# solar-counter-v1_0.net
KiCad netlist of a schematic drawn in EAGLE
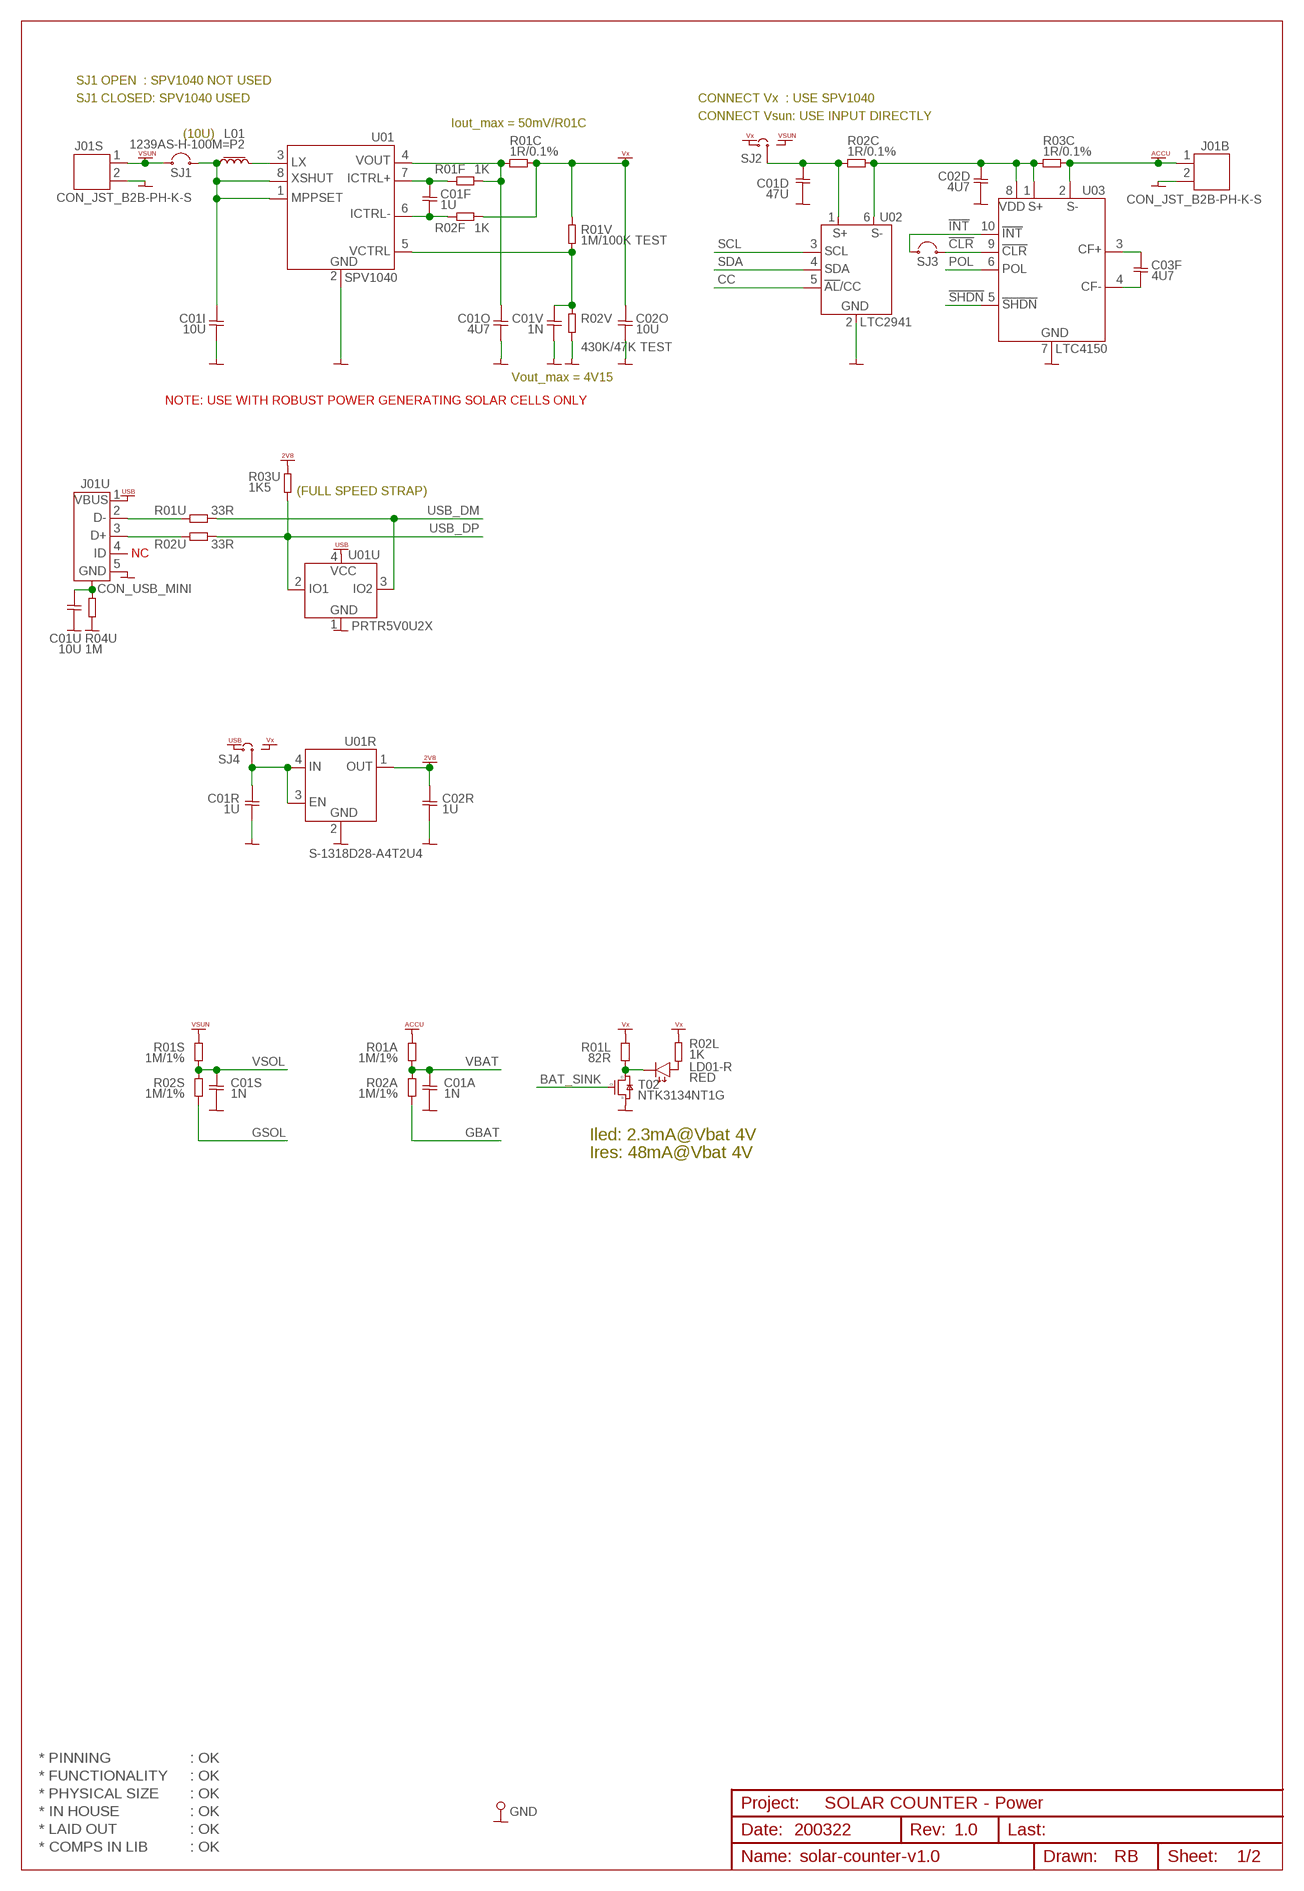
[diagram p0: schematic, sheet 1]
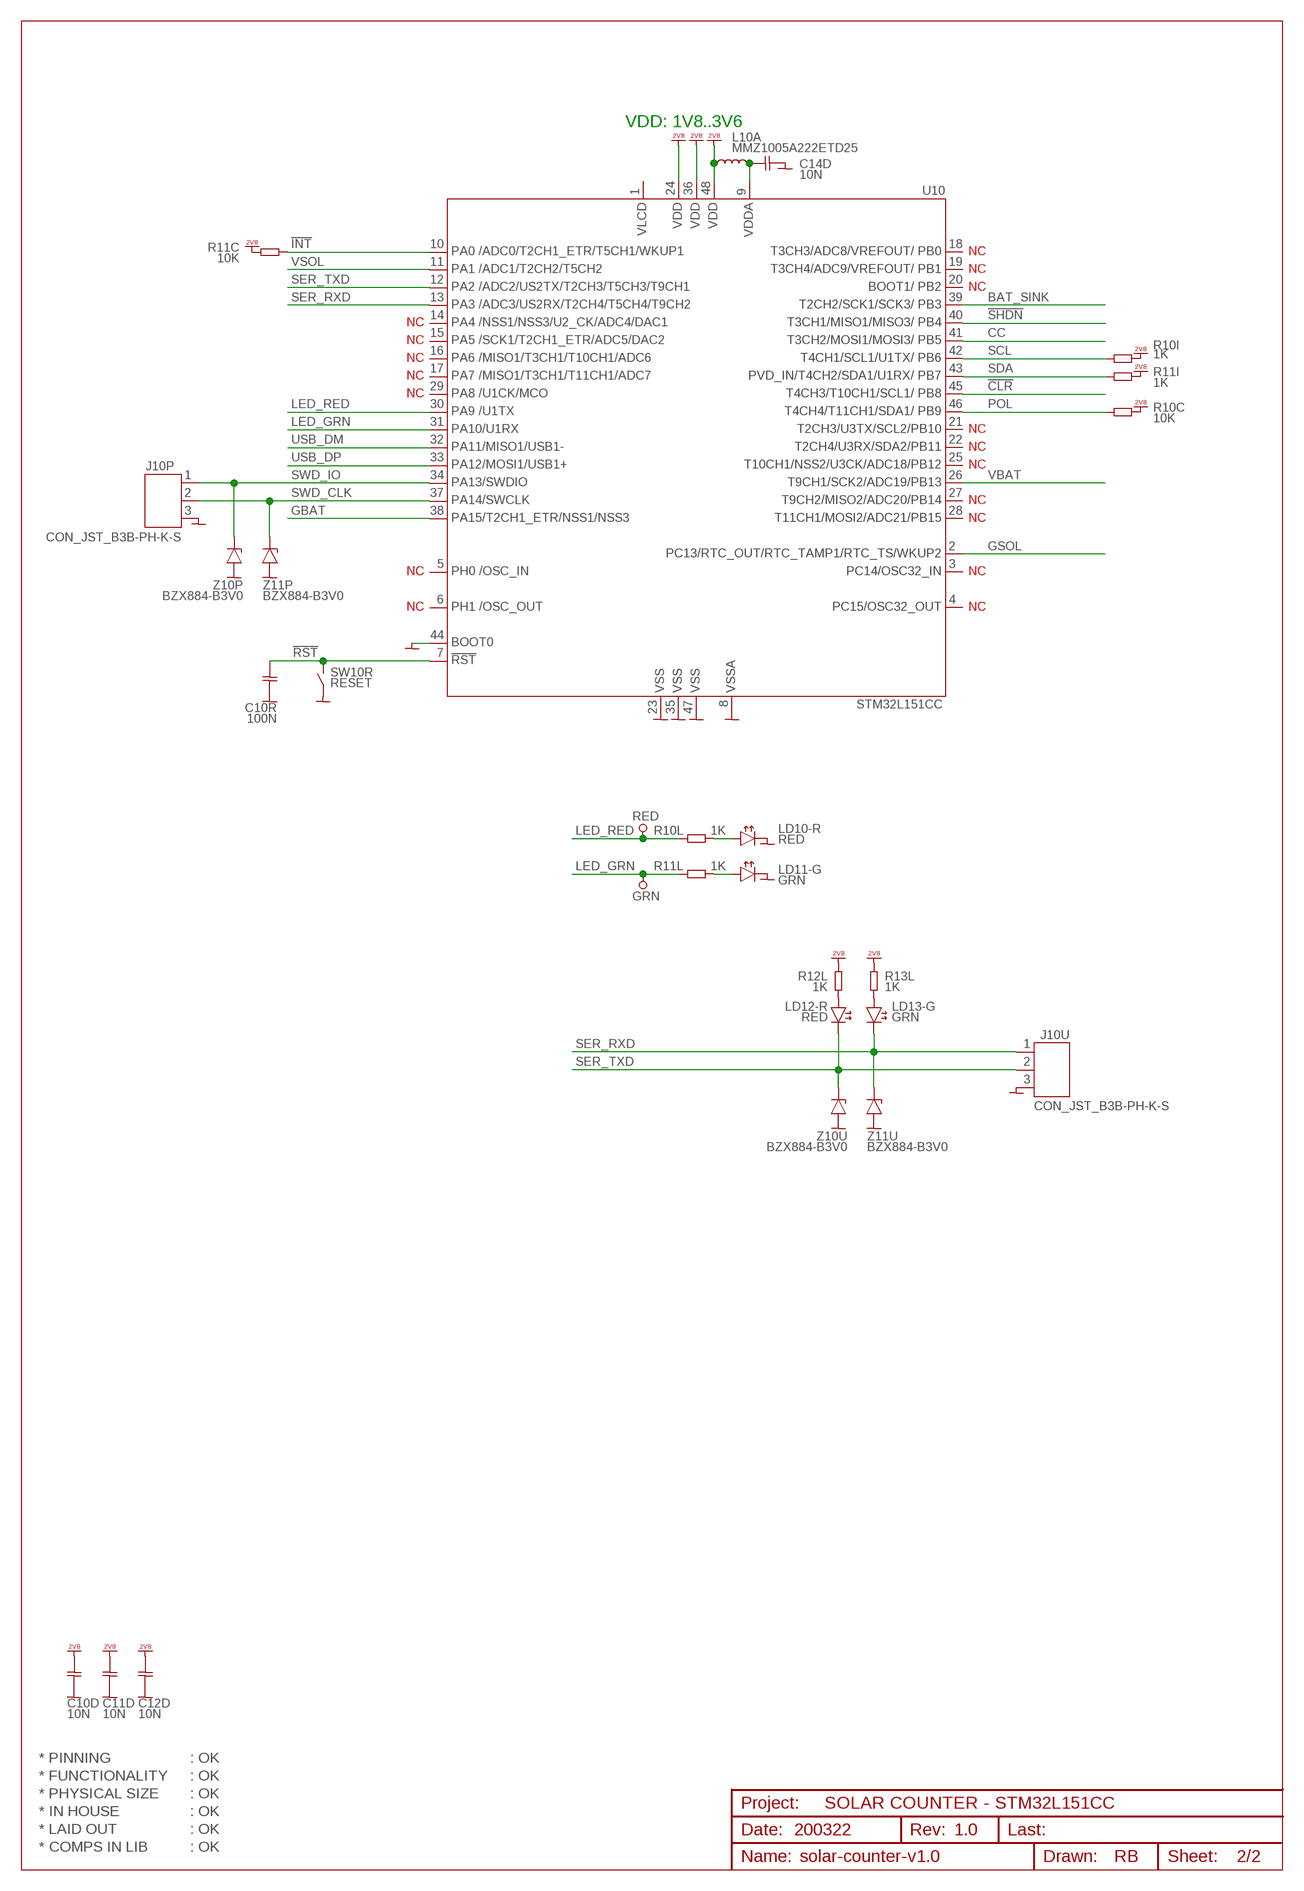
[diagram p1: schematic, sheet 2]

(export (version "E")
  (design (tool "Eeschema 10.0.6"))
  (components
    (comp (ref "C10D")
      (value "10N")
      (footprint "eagle-import:CAP0402")
      (libsource (lib "eagle-import") (part "CAP0402"))
    )
    (comp (ref "C10R")
      (value "100N")
      (footprint "eagle-import:CAP0402")
      (libsource (lib "eagle-import") (part "CAP0402"))
    )
    (comp (ref "C11D")
      (value "10N")
      (footprint "eagle-import:CAP0402")
      (libsource (lib "eagle-import") (part "CAP0402"))
    )
    (comp (ref "C12D")
      (value "10N")
      (footprint "eagle-import:CAP0402")
      (libsource (lib "eagle-import") (part "CAP0402"))
    )
    (comp (ref "C14D")
      (value "10N")
      (footprint "eagle-import:CAP0402")
      (libsource (lib "eagle-import") (part "CAP0402"))
    )
    (comp (ref "GRN")
      (value "PIN_TEST_0.6MM")
      (footprint "eagle-import:HOLE_PTH_0.6MM")
      (libsource (lib "eagle-import") (part "PIN_TEST_0.6MM"))
    )
    (comp (ref "J10P")
      (value "CON_JST_B3B-PH-K-S")
      (footprint "eagle-import:CON_JST_B3B-PH-K-S")
      (libsource (lib "eagle-import") (part "CON_JST_B3B-PH-K-S"))
    )
    (comp (ref "J10U")
      (value "CON_JST_B3B-PH-K-S")
      (footprint "eagle-import:CON_JST_B3B-PH-K-S")
      (libsource (lib "eagle-import") (part "CON_JST_B3B-PH-K-S"))
    )
    (comp (ref "L10A")
      (value "MMZ1005A222ETD25")
      (footprint "eagle-import:L_0402")
      (libsource (lib "eagle-import") (part "L_0402"))
    )
    (comp (ref "LD10-R")
      (value "RED")
      (footprint "eagle-import:LED_SMD_0402")
      (libsource (lib "eagle-import") (part "LED_SMD_0402"))
    )
    (comp (ref "LD11-G")
      (value "GRN")
      (footprint "eagle-import:LED_SMD_0402")
      (libsource (lib "eagle-import") (part "LED_SMD_0402"))
    )
    (comp (ref "LD12-R")
      (value "RED")
      (footprint "eagle-import:LED_SMD_0402")
      (libsource (lib "eagle-import") (part "LED_SMD_0402"))
    )
    (comp (ref "LD13-G")
      (value "GRN")
      (footprint "eagle-import:LED_SMD_0402")
      (libsource (lib "eagle-import") (part "LED_SMD_0402"))
    )
    (comp (ref "R10C")
      (value "10K")
      (footprint "eagle-import:RES0402")
      (libsource (lib "eagle-import") (part "RES0402"))
    )
    (comp (ref "R10I")
      (value "1K")
      (footprint "eagle-import:RES0402")
      (libsource (lib "eagle-import") (part "RES0402"))
    )
    (comp (ref "R10L")
      (value "1K")
      (footprint "eagle-import:RES0402")
      (libsource (lib "eagle-import") (part "RES0402"))
    )
    (comp (ref "R11C")
      (value "10K")
      (footprint "eagle-import:RES0402")
      (libsource (lib "eagle-import") (part "RES0402"))
    )
    (comp (ref "R11I")
      (value "1K")
      (footprint "eagle-import:RES0402")
      (libsource (lib "eagle-import") (part "RES0402"))
    )
    (comp (ref "R11L")
      (value "1K")
      (footprint "eagle-import:RES0402")
      (libsource (lib "eagle-import") (part "RES0402"))
    )
    (comp (ref "R12L")
      (value "1K")
      (footprint "eagle-import:RES0402")
      (libsource (lib "eagle-import") (part "RES0402"))
    )
    (comp (ref "R13L")
      (value "1K")
      (footprint "eagle-import:RES0402")
      (libsource (lib "eagle-import") (part "RES0402"))
    )
    (comp (ref "RED")
      (value "PIN_TEST_0.6MM")
      (footprint "eagle-import:HOLE_PTH_0.6MM")
      (libsource (lib "eagle-import") (part "PIN_TEST_0.6MM"))
    )
    (comp (ref "SW10R")
      (value "RESET")
      (footprint "eagle-import:SWITCH_SMD_PBUTTON_2P")
      (libsource (lib "eagle-import") (part "SWITCH_PUSHBUTTON"))
    )
    (comp (ref "U10")
      (value "STM32L151CC")
      (footprint "eagle-import:LQFP48")
      (libsource (lib "eagle-import") (part "STM32L151CC"))
    )
    (comp (ref "Z10P")
      (value "BZX884-B3V0")
      (footprint "eagle-import:ZENER_SOD923")
      (libsource (lib "eagle-import") (part "ZENER_SOD923"))
    )
    (comp (ref "Z10U")
      (value "BZX884-B3V0")
      (footprint "eagle-import:ZENER_SOD923")
      (libsource (lib "eagle-import") (part "ZENER_SOD923"))
    )
    (comp (ref "Z11P")
      (value "BZX884-B3V0")
      (footprint "eagle-import:ZENER_SOD923")
      (libsource (lib "eagle-import") (part "ZENER_SOD923"))
    )
    (comp (ref "Z11U")
      (value "BZX884-B3V0")
      (footprint "eagle-import:ZENER_SOD923")
      (libsource (lib "eagle-import") (part "ZENER_SOD923"))
    )
    (comp (ref "C01A")
      (value "1N")
      (footprint "eagle-import:CAP0402")
      (libsource (lib "eagle-import") (part "CAP0402"))
    )
    (comp (ref "C01D")
      (value "47U")
      (footprint "eagle-import:CAP0603")
      (libsource (lib "eagle-import") (part "CAP0603"))
    )
    (comp (ref "C01F")
      (value "1U")
      (footprint "eagle-import:CAP0402")
      (libsource (lib "eagle-import") (part "CAP0402"))
    )
    (comp (ref "C01I")
      (value "10U")
      (footprint "eagle-import:CAP0603")
      (libsource (lib "eagle-import") (part "CAP0603"))
    )
    (comp (ref "C01O")
      (value "4U7")
      (footprint "eagle-import:CAP0402")
      (libsource (lib "eagle-import") (part "CAP0402"))
    )
    (comp (ref "C01R")
      (value "1U")
      (footprint "eagle-import:CAP0402")
      (libsource (lib "eagle-import") (part "CAP0402"))
    )
    (comp (ref "C01S")
      (value "1N")
      (footprint "eagle-import:CAP0402")
      (libsource (lib "eagle-import") (part "CAP0402"))
    )
    (comp (ref "C01U")
      (value "10U")
      (footprint "eagle-import:CAP0603")
      (libsource (lib "eagle-import") (part "CAP0603"))
    )
    (comp (ref "C01V")
      (value "1N")
      (footprint "eagle-import:CAP0402")
      (libsource (lib "eagle-import") (part "CAP0402"))
    )
    (comp (ref "C02D")
      (value "4U7")
      (footprint "eagle-import:CAP0402")
      (libsource (lib "eagle-import") (part "CAP0402"))
    )
    (comp (ref "C02O")
      (value "10U")
      (footprint "eagle-import:CAP0402")
      (libsource (lib "eagle-import") (part "CAP0402"))
    )
    (comp (ref "C02R")
      (value "1U")
      (footprint "eagle-import:CAP0402")
      (libsource (lib "eagle-import") (part "CAP0402"))
    )
    (comp (ref "C03F")
      (value "4U7")
      (footprint "eagle-import:CAP0402")
      (libsource (lib "eagle-import") (part "CAP0402"))
    )
    (comp (ref "GND")
      (value "PIN_TEST")
      (footprint "eagle-import:HOLE_PTH_0.8MM")
      (libsource (lib "eagle-import") (part "PIN_TEST"))
    )
    (comp (ref "J01B")
      (value "CON_JST_B2B-PH-K-S")
      (footprint "eagle-import:CON_JST_B2B-PH-K-S")
      (libsource (lib "eagle-import") (part "CON_JST_B2B-PH-K-S"))
    )
    (comp (ref "J01S")
      (value "CON_JST_B2B-PH-K-S")
      (footprint "eagle-import:CON_JST_B2B-PH-K-S")
      (libsource (lib "eagle-import") (part "CON_JST_B2B-PH-K-S"))
    )
    (comp (ref "J01U")
      (value "CON_USB_MINI")
      (footprint "eagle-import:CON_USB-B_MINI")
      (libsource (lib "eagle-import") (part "CON_USB_MINI"))
    )
    (comp (ref "L01")
      (value "1239AS-H-100M=P2")
      (footprint "eagle-import:L_1008")
      (libsource (lib "eagle-import") (part "L_1008"))
    )
    (comp (ref "LD01-R")
      (value "RED")
      (footprint "eagle-import:LED_SMD_0402")
      (libsource (lib "eagle-import") (part "LED_SMD_0402"))
    )
    (comp (ref "R01A")
      (value "1M/1%")
      (footprint "eagle-import:RES0402")
      (libsource (lib "eagle-import") (part "RES0402"))
    )
    (comp (ref "R01C")
      (value "1R/0.1%")
      (footprint "eagle-import:RES0402")
      (libsource (lib "eagle-import") (part "RES0402"))
    )
    (comp (ref "R01F")
      (value "1K")
      (footprint "eagle-import:RES0402")
      (libsource (lib "eagle-import") (part "RES0402"))
    )
    (comp (ref "R01L")
      (value "82R")
      (footprint "eagle-import:RES0402")
      (libsource (lib "eagle-import") (part "RES0402"))
    )
    (comp (ref "R01S")
      (value "1M/1%")
      (footprint "eagle-import:RES0402")
      (libsource (lib "eagle-import") (part "RES0402"))
    )
    (comp (ref "R01U")
      (value "33R")
      (footprint "eagle-import:RES0402")
      (libsource (lib "eagle-import") (part "RES0402"))
    )
    (comp (ref "R01V")
      (value "1M/100K TEST")
      (footprint "eagle-import:RES0402")
      (libsource (lib "eagle-import") (part "RES0402"))
    )
    (comp (ref "R02A")
      (value "1M/1%")
      (footprint "eagle-import:RES0402")
      (libsource (lib "eagle-import") (part "RES0402"))
    )
    (comp (ref "R02C")
      (value "1R/0.1%")
      (footprint "eagle-import:RES0402")
      (libsource (lib "eagle-import") (part "RES0402"))
    )
    (comp (ref "R02F")
      (value "1K")
      (footprint "eagle-import:RES0402")
      (libsource (lib "eagle-import") (part "RES0402"))
    )
    (comp (ref "R02L")
      (value "1K")
      (footprint "eagle-import:RES0402")
      (libsource (lib "eagle-import") (part "RES0402"))
    )
    (comp (ref "R02S")
      (value "1M/1%")
      (footprint "eagle-import:RES0402")
      (libsource (lib "eagle-import") (part "RES0402"))
    )
    (comp (ref "R02U")
      (value "33R")
      (footprint "eagle-import:RES0402")
      (libsource (lib "eagle-import") (part "RES0402"))
    )
    (comp (ref "R02V")
      (value "430K/47K TEST")
      (footprint "eagle-import:RES0402")
      (libsource (lib "eagle-import") (part "RES0402"))
    )
    (comp (ref "R03C")
      (value "1R/0.1%")
      (footprint "eagle-import:RES0402")
      (libsource (lib "eagle-import") (part "RES0402"))
    )
    (comp (ref "R03U")
      (value "1K5")
      (footprint "eagle-import:RES0402")
      (libsource (lib "eagle-import") (part "RES0402"))
    )
    (comp (ref "R04U")
      (value "1M")
      (footprint "eagle-import:RES0603")
      (libsource (lib "eagle-import") (part "RES0603"))
    )
    (comp (ref "SJ1")
      (value "SJ2SJ2-S")
      (footprint "eagle-import:SJ2-S")
      (libsource (lib "eagle-import") (part "SJ2SJ2-S"))
    )
    (comp (ref "SJ2")
      (value "SJ3SJ3-S")
      (footprint "eagle-import:SJ3-S")
      (libsource (lib "eagle-import") (part "SJ3SJ3-S"))
    )
    (comp (ref "SJ3")
      (value "SJ2SJ2-S")
      (footprint "eagle-import:SJ2-S")
      (libsource (lib "eagle-import") (part "SJ2SJ2-S"))
    )
    (comp (ref "SJ4")
      (value "SJ3SJ3-S")
      (footprint "eagle-import:SJ3-S")
      (libsource (lib "eagle-import") (part "SJ3SJ3-S"))
    )
    (comp (ref "T02")
      (value "NTK3134NT1G")
      (footprint "eagle-import:NFET_SOT723")
      (libsource (lib "eagle-import") (part "NFET_SOT723"))
    )
    (comp (ref "U01")
      (value "SPV1040")
      (footprint "eagle-import:TSSOP8")
      (libsource (lib "eagle-import") (part "SPV1040"))
    )
    (comp (ref "U01R")
      (value "S-1318D28-A4T2U4")
      (footprint "eagle-import:HSNT-4-B")
      (libsource (lib "eagle-import") (part "S-1318D28-A4T2U4"))
    )
    (comp (ref "U01U")
      (value "PRTR5V0U2X")
      (footprint "eagle-import:SOT143B")
      (libsource (lib "eagle-import") (part "PRTR5V0U2X"))
    )
    (comp (ref "U02")
      (value "LTC2941")
      (footprint "eagle-import:DFN6_2X3MM_NO-EXPOSED")
      (libsource (lib "eagle-import") (part "LTC2941"))
    )
    (comp (ref "U03")
      (value "LTC4150")
      (footprint "eagle-import:MSOP10")
      (libsource (lib "eagle-import") (part "LTC4150"))
    )
  )
  (nets
    (net (code "1") (name "ACCU") (class "Default")
      (node (ref "J01B") (pin "1") (pinfunction "1_1") (pintype "passive"))
      (node (ref "R01A") (pin "2") (pinfunction "2_2") (pintype "passive"))
      (node (ref "R03C") (pin "2") (pinfunction "2_2") (pintype "passive"))
      (node (ref "U03") (pin "2") (pinfunction "2.SENSE-_2") (pintype "passive"))
    )
    (net (code "2") (name "BAT_SINK") (class "Default")
      (node (ref "T02") (pin "1") (pinfunction "1.G_1") (pintype "passive"))
      (node (ref "U10") (pin "39") (pinfunction "39.PB3_39") (pintype "passive"))
    )
    (net (code "3") (name "CC") (class "Default")
      (node (ref "U02") (pin "5") (pinfunction "5.AL/CC_5") (pintype "passive"))
      (node (ref "U10") (pin "41") (pinfunction "41.PB5_41") (pintype "passive"))
    )
    (net (code "4") (name "GBAT") (class "Default")
      (node (ref "R02A") (pin "1") (pinfunction "1_1") (pintype "passive"))
      (node (ref "U10") (pin "38") (pinfunction "38.PA15_38") (pintype "passive"))
    )
    (net (code "5") (name "GND") (class "Default")
      (node (ref "C01A") (pin "2") (pinfunction "2_2") (pintype "passive"))
      (node (ref "C01D") (pin "2") (pinfunction "2_2") (pintype "passive"))
      (node (ref "C01I") (pin "2") (pinfunction "2_2") (pintype "passive"))
      (node (ref "C01O") (pin "2") (pinfunction "2_2") (pintype "passive"))
      (node (ref "C01R") (pin "2") (pinfunction "2_2") (pintype "passive"))
      (node (ref "C01S") (pin "2") (pinfunction "2_2") (pintype "passive"))
      (node (ref "C01U") (pin "2") (pinfunction "2_2") (pintype "passive"))
      (node (ref "C01V") (pin "2") (pinfunction "2_2") (pintype "passive"))
      (node (ref "C02D") (pin "2") (pinfunction "2_2") (pintype "passive"))
      (node (ref "C02O") (pin "2") (pinfunction "2_2") (pintype "passive"))
      (node (ref "C02R") (pin "2") (pinfunction "2_2") (pintype "passive"))
      (node (ref "C10D") (pin "2") (pinfunction "2_2") (pintype "passive"))
      (node (ref "C10R") (pin "2") (pinfunction "2_2") (pintype "passive"))
      (node (ref "C11D") (pin "2") (pinfunction "2_2") (pintype "passive"))
      (node (ref "C12D") (pin "2") (pinfunction "2_2") (pintype "passive"))
      (node (ref "C14D") (pin "2") (pinfunction "2_2") (pintype "passive"))
      (node (ref "GND") (pin "1") (pinfunction "P$1_1") (pintype "passive"))
      (node (ref "J01B") (pin "2") (pinfunction "2_2") (pintype "passive"))
      (node (ref "J01S") (pin "2") (pinfunction "2_2") (pintype "passive"))
      (node (ref "J01U") (pin "5") (pinfunction "5.GND_5") (pintype "passive"))
      (node (ref "J10P") (pin "3") (pinfunction "3_3") (pintype "passive"))
      (node (ref "J10U") (pin "3") (pinfunction "3_3") (pintype "passive"))
      (node (ref "LD10-R") (pin "C") (pinfunction "C_C") (pintype "passive"))
      (node (ref "LD11-G") (pin "C") (pinfunction "C_C") (pintype "passive"))
      (node (ref "R02V") (pin "2") (pinfunction "2_2") (pintype "passive"))
      (node (ref "R04U") (pin "2") (pinfunction "2_2") (pintype "passive"))
      (node (ref "SW10R") (pin "2") (pinfunction "3-4_2") (pintype "passive"))
      (node (ref "T02") (pin "2") (pinfunction "2.S_2") (pintype "passive"))
      (node (ref "U01") (pin "2") (pinfunction "2.GND_2") (pintype "passive"))
      (node (ref "U01R") (pin "2") (pinfunction "2.GND_2") (pintype "passive"))
      (node (ref "U01R") (pin "5") (pinfunction "2.GND_5") (pintype "passive"))
      (node (ref "U01U") (pin "1") (pinfunction "1.GND_1") (pintype "passive"))
      (node (ref "U02") (pin "2") (pinfunction "2.GND_2") (pintype "passive"))
      (node (ref "U03") (pin "7") (pinfunction "7.GND_7") (pintype "passive"))
      (node (ref "U10") (pin "23") (pinfunction "23.GND_23") (pintype "passive"))
      (node (ref "U10") (pin "35") (pinfunction "35.GND_35") (pintype "passive"))
      (node (ref "U10") (pin "44") (pinfunction "44.BOOT0_44") (pintype "passive"))
      (node (ref "U10") (pin "47") (pinfunction "47.GND_47") (pintype "passive"))
      (node (ref "U10") (pin "8") (pinfunction "8.GND_8") (pintype "passive"))
      (node (ref "Z10P") (pin "2") (pinfunction "A_2") (pintype "passive"))
      (node (ref "Z10U") (pin "2") (pinfunction "A_2") (pintype "passive"))
      (node (ref "Z11P") (pin "2") (pinfunction "A_2") (pintype "passive"))
      (node (ref "Z11U") (pin "2") (pinfunction "A_2") (pintype "passive"))
    )
    (net (code "6") (name "GSOL") (class "Default")
      (node (ref "R02S") (pin "1") (pinfunction "1_1") (pintype "passive"))
      (node (ref "U10") (pin "2") (pinfunction "2.PC13_2") (pintype "passive"))
    )
    (net (code "7") (name "LED_GRN") (class "Default")
      (node (ref "GRN") (pin "1") (pinfunction "P$1_1") (pintype "passive"))
      (node (ref "R11L") (pin "1") (pinfunction "1_1") (pintype "passive"))
      (node (ref "U10") (pin "31") (pinfunction "31.PA10_31") (pintype "passive"))
    )
    (net (code "8") (name "LED_RED") (class "Default")
      (node (ref "R10L") (pin "1") (pinfunction "1_1") (pintype "passive"))
      (node (ref "RED") (pin "1") (pinfunction "P$1_1") (pintype "passive"))
      (node (ref "U10") (pin "30") (pinfunction "30.PA9_30") (pintype "passive"))
    )
    (net (code "9") (name "Net-(C01U-Pad1)") (class "Default")
      (node (ref "C01U") (pin "1") (pinfunction "1_1") (pintype "passive"))
      (node (ref "J01U") (pin "CASE1") (pinfunction "CASE_CASE1") (pintype "passive"))
      (node (ref "J01U") (pin "CASE2") (pinfunction "CASE_CASE2") (pintype "passive"))
      (node (ref "J01U") (pin "CASE3") (pinfunction "CASE_CASE3") (pintype "passive"))
      (node (ref "J01U") (pin "CASE4") (pinfunction "CASE_CASE4") (pintype "passive"))
      (node (ref "R04U") (pin "1") (pinfunction "1_1") (pintype "passive"))
    )
    (net (code "10") (name "Net-(J01U-2.D-)") (class "Default")
      (node (ref "J01U") (pin "2") (pinfunction "2.D-_2") (pintype "passive"))
      (node (ref "R01U") (pin "1") (pinfunction "1_1") (pintype "passive"))
    )
    (net (code "11") (name "Net-(J01U-3.D+)") (class "Default")
      (node (ref "J01U") (pin "3") (pinfunction "3.D+_3") (pintype "passive"))
      (node (ref "R02U") (pin "1") (pinfunction "1_1") (pintype "passive"))
    )
    (net (code "12") (name "Net-(LD01-R-PadA)") (class "Default")
      (node (ref "LD01-R") (pin "A") (pinfunction "A_A") (pintype "passive"))
      (node (ref "R02L") (pin "2") (pinfunction "2_2") (pintype "passive"))
    )
    (net (code "13") (name "Net-(LD10-R-PadA)") (class "Default")
      (node (ref "LD10-R") (pin "A") (pinfunction "A_A") (pintype "passive"))
      (node (ref "R10L") (pin "2") (pinfunction "2_2") (pintype "passive"))
    )
    (net (code "14") (name "Net-(LD11-G-PadA)") (class "Default")
      (node (ref "LD11-G") (pin "A") (pinfunction "A_A") (pintype "passive"))
      (node (ref "R11L") (pin "2") (pinfunction "2_2") (pintype "passive"))
    )
    (net (code "15") (name "Net-(LD12-R-PadA)") (class "Default")
      (node (ref "LD12-R") (pin "A") (pinfunction "A_A") (pintype "passive"))
      (node (ref "R12L") (pin "2") (pinfunction "2_2") (pintype "passive"))
    )
    (net (code "16") (name "Net-(LD13-G-PadA)") (class "Default")
      (node (ref "LD13-G") (pin "A") (pinfunction "A_A") (pintype "passive"))
      (node (ref "R13L") (pin "2") (pinfunction "2_2") (pintype "passive"))
    )
    (net (code "17") (name "Net-(SJ1-P$2)") (class "Default")
      (node (ref "C01I") (pin "1") (pinfunction "1_1") (pintype "passive"))
      (node (ref "L01") (pin "2") (pinfunction "2_2") (pintype "passive"))
      (node (ref "SJ1") (pin "2") (pinfunction "P$2_2") (pintype "passive"))
      (node (ref "U01") (pin "1") (pinfunction "1.MPPSET_1") (pintype "passive"))
      (node (ref "U01") (pin "8") (pinfunction "8.XSHUT_8") (pintype "passive"))
    )
    (net (code "18") (name "Net-(T02-3.D)") (class "Default")
      (node (ref "LD01-R") (pin "C") (pinfunction "C_C") (pintype "passive"))
      (node (ref "R01L") (pin "1") (pinfunction "1_1") (pintype "passive"))
      (node (ref "T02") (pin "3") (pinfunction "3.D_3") (pintype "passive"))
    )
    (net (code "19") (name "Net-(U01-3.LX)") (class "Default")
      (node (ref "L01") (pin "1") (pinfunction "1_1") (pintype "passive"))
      (node (ref "U01") (pin "3") (pinfunction "3.LX_3") (pintype "passive"))
    )
    (net (code "20") (name "Net-(U01-4.VOUT)") (class "Default")
      (node (ref "C01O") (pin "1") (pinfunction "1_1") (pintype "passive"))
      (node (ref "R01C") (pin "1") (pinfunction "1_1") (pintype "passive"))
      (node (ref "R01F") (pin "1") (pinfunction "1_1") (pintype "passive"))
      (node (ref "U01") (pin "4") (pinfunction "4.VOUT_4") (pintype "passive"))
    )
    (net (code "21") (name "Net-(U01-5.VCTRL)") (class "Default")
      (node (ref "C01V") (pin "1") (pinfunction "1_1") (pintype "passive"))
      (node (ref "R01V") (pin "2") (pinfunction "2_2") (pintype "passive"))
      (node (ref "R02V") (pin "1") (pinfunction "1_1") (pintype "passive"))
      (node (ref "U01") (pin "5") (pinfunction "5.VCTRL_5") (pintype "passive"))
    )
    (net (code "22") (name "Net-(U01-6.ICTRL-)") (class "Default")
      (node (ref "C01F") (pin "2") (pinfunction "2_2") (pintype "passive"))
      (node (ref "R02F") (pin "2") (pinfunction "2_2") (pintype "passive"))
      (node (ref "U01") (pin "6") (pinfunction "6.ICTRL-_6") (pintype "passive"))
    )
    (net (code "23") (name "Net-(U01-7.ICTRL+)") (class "Default")
      (node (ref "C01F") (pin "1") (pinfunction "1_1") (pintype "passive"))
      (node (ref "R01F") (pin "2") (pinfunction "2_2") (pintype "passive"))
      (node (ref "U01") (pin "7") (pinfunction "7.ICTRL+_7") (pintype "passive"))
    )
    (net (code "24") (name "Net-(U01R-3.EN)") (class "Default")
      (node (ref "C01R") (pin "1") (pinfunction "1_1") (pintype "passive"))
      (node (ref "SJ4") (pin "2") (pinfunction "2_2") (pintype "passive"))
      (node (ref "U01R") (pin "3") (pinfunction "3.EN_3") (pintype "passive"))
      (node (ref "U01R") (pin "4") (pinfunction "4.IN_4") (pintype "passive"))
    )
    (net (code "25") (name "Net-(U02-1.SENSE+)") (class "Default")
      (node (ref "C01D") (pin "1") (pinfunction "1_1") (pintype "passive"))
      (node (ref "R02C") (pin "1") (pinfunction "1_1") (pintype "passive"))
      (node (ref "SJ2") (pin "2") (pinfunction "2_2") (pintype "passive"))
      (node (ref "U02") (pin "1") (pinfunction "1.SENSE+_1") (pintype "passive"))
    )
    (net (code "26") (name "Net-(U02-6.SENSE-)") (class "Default")
      (node (ref "C02D") (pin "1") (pinfunction "1_1") (pintype "passive"))
      (node (ref "R02C") (pin "2") (pinfunction "2_2") (pintype "passive"))
      (node (ref "R03C") (pin "1") (pinfunction "1_1") (pintype "passive"))
      (node (ref "U02") (pin "6") (pinfunction "6.SENSE-_6") (pintype "passive"))
      (node (ref "U03") (pin "1") (pinfunction "1.SENSE+_1") (pintype "passive"))
      (node (ref "U03") (pin "8") (pinfunction "8.VDD_8") (pintype "passive"))
    )
    (net (code "27") (name "Net-(U03-3.CF+)") (class "Default")
      (node (ref "C03F") (pin "1") (pinfunction "1_1") (pintype "passive"))
      (node (ref "U03") (pin "3") (pinfunction "3.CF+_3") (pintype "passive"))
    )
    (net (code "28") (name "Net-(U03-4.CF-)") (class "Default")
      (node (ref "C03F") (pin "2") (pinfunction "2_2") (pintype "passive"))
      (node (ref "U03") (pin "4") (pinfunction "4.CF-_4") (pintype "passive"))
    )
    (net (code "29") (name "Net-(U10-9.VDD)") (class "Default")
      (node (ref "C14D") (pin "1") (pinfunction "1_1") (pintype "passive"))
      (node (ref "L10A") (pin "2") (pinfunction "2_2") (pintype "passive"))
      (node (ref "U10") (pin "9") (pinfunction "9.VDD_9") (pintype "passive"))
    )
    (net (code "30") (name "POL") (class "Default")
      (node (ref "R10C") (pin "1") (pinfunction "1_1") (pintype "passive"))
      (node (ref "U03") (pin "6") (pinfunction "6.POL_6") (pintype "passive"))
      (node (ref "U10") (pin "46") (pinfunction "46.PB9_46") (pintype "passive"))
    )
    (net (code "31") (name "SCL") (class "Default")
      (node (ref "R10I") (pin "1") (pinfunction "1_1") (pintype "passive"))
      (node (ref "U02") (pin "3") (pinfunction "3.SCL_3") (pintype "passive"))
      (node (ref "U10") (pin "42") (pinfunction "42.PB6_42") (pintype "passive"))
    )
    (net (code "32") (name "SDA") (class "Default")
      (node (ref "R11I") (pin "1") (pinfunction "1_1") (pintype "passive"))
      (node (ref "U02") (pin "4") (pinfunction "4.SDA_4") (pintype "passive"))
      (node (ref "U10") (pin "43") (pinfunction "43.PB7_43") (pintype "passive"))
    )
    (net (code "33") (name "SER_RXD") (class "Default")
      (node (ref "J10U") (pin "1") (pinfunction "1_1") (pintype "passive"))
      (node (ref "LD13-G") (pin "C") (pinfunction "C_C") (pintype "passive"))
      (node (ref "U10") (pin "13") (pinfunction "13.PA3_13") (pintype "passive"))
      (node (ref "Z11U") (pin "1") (pinfunction "C_1") (pintype "passive"))
    )
    (net (code "34") (name "SER_TXD") (class "Default")
      (node (ref "J10U") (pin "2") (pinfunction "2_2") (pintype "passive"))
      (node (ref "LD12-R") (pin "C") (pinfunction "C_C") (pintype "passive"))
      (node (ref "U10") (pin "12") (pinfunction "12.PA2_12") (pintype "passive"))
      (node (ref "Z10U") (pin "1") (pinfunction "C_1") (pintype "passive"))
    )
    (net (code "35") (name "SWD_CLK") (class "Default")
      (node (ref "J10P") (pin "2") (pinfunction "2_2") (pintype "passive"))
      (node (ref "U10") (pin "37") (pinfunction "37.PA14_37") (pintype "passive"))
      (node (ref "Z11P") (pin "1") (pinfunction "C_1") (pintype "passive"))
    )
    (net (code "36") (name "SWD_IO") (class "Default")
      (node (ref "J10P") (pin "1") (pinfunction "1_1") (pintype "passive"))
      (node (ref "U10") (pin "34") (pinfunction "34.PA13_34") (pintype "passive"))
      (node (ref "Z10P") (pin "1") (pinfunction "C_1") (pintype "passive"))
    )
    (net (code "37") (name "USB_DM") (class "Default")
      (node (ref "R01U") (pin "2") (pinfunction "2_2") (pintype "passive"))
      (node (ref "U01U") (pin "3") (pinfunction "3.IO2_3") (pintype "passive"))
      (node (ref "U10") (pin "32") (pinfunction "32.PA11_32") (pintype "passive"))
    )
    (net (code "38") (name "USB_DP") (class "Default")
      (node (ref "R02U") (pin "2") (pinfunction "2_2") (pintype "passive"))
      (node (ref "R03U") (pin "1") (pinfunction "1_1") (pintype "passive"))
      (node (ref "U01U") (pin "2") (pinfunction "2.IO1_2") (pintype "passive"))
      (node (ref "U10") (pin "33") (pinfunction "33.PA12_33") (pintype "passive"))
    )
    (net (code "39") (name "VBAT") (class "Default")
      (node (ref "C01A") (pin "1") (pinfunction "1_1") (pintype "passive"))
      (node (ref "R01A") (pin "1") (pinfunction "1_1") (pintype "passive"))
      (node (ref "R02A") (pin "2") (pinfunction "2_2") (pintype "passive"))
      (node (ref "U10") (pin "26") (pinfunction "26.PB13_26") (pintype "passive"))
    )
    (net (code "40") (name "VCC_POWER-USB") (class "Default")
      (node (ref "J01U") (pin "1") (pinfunction "1.VBUS_1") (pintype "passive"))
      (node (ref "SJ4") (pin "1") (pinfunction "1_1") (pintype "passive"))
      (node (ref "U01U") (pin "4") (pinfunction "4.VCC_4") (pintype "passive"))
    )
    (net (code "41") (name "VDD_2V8") (class "Default")
      (node (ref "C02R") (pin "1") (pinfunction "1_1") (pintype "passive"))
      (node (ref "C10D") (pin "1") (pinfunction "1_1") (pintype "passive"))
      (node (ref "C11D") (pin "1") (pinfunction "1_1") (pintype "passive"))
      (node (ref "C12D") (pin "1") (pinfunction "1_1") (pintype "passive"))
      (node (ref "L10A") (pin "1") (pinfunction "1_1") (pintype "passive"))
      (node (ref "R03U") (pin "2") (pinfunction "2_2") (pintype "passive"))
      (node (ref "R10C") (pin "2") (pinfunction "2_2") (pintype "passive"))
      (node (ref "R10I") (pin "2") (pinfunction "2_2") (pintype "passive"))
      (node (ref "R11C") (pin "2") (pinfunction "2_2") (pintype "passive"))
      (node (ref "R11I") (pin "2") (pinfunction "2_2") (pintype "passive"))
      (node (ref "R12L") (pin "1") (pinfunction "1_1") (pintype "passive"))
      (node (ref "R13L") (pin "1") (pinfunction "1_1") (pintype "passive"))
      (node (ref "U01R") (pin "1") (pinfunction "1.OUT_1") (pintype "passive"))
      (node (ref "U10") (pin "24") (pinfunction "24.VDD_24") (pintype "passive"))
      (node (ref "U10") (pin "36") (pinfunction "36.VDD_36") (pintype "passive"))
      (node (ref "U10") (pin "48") (pinfunction "48.VDD_48") (pintype "passive"))
    )
    (net (code "42") (name "VSOL") (class "Default")
      (node (ref "C01S") (pin "1") (pinfunction "1_1") (pintype "passive"))
      (node (ref "R01S") (pin "1") (pinfunction "1_1") (pintype "passive"))
      (node (ref "R02S") (pin "2") (pinfunction "2_2") (pintype "passive"))
      (node (ref "U10") (pin "11") (pinfunction "11.PA1_11") (pintype "passive"))
    )
    (net (code "43") (name "VSUN") (class "Default")
      (node (ref "J01S") (pin "1") (pinfunction "1_1") (pintype "passive"))
      (node (ref "R01S") (pin "2") (pinfunction "2_2") (pintype "passive"))
      (node (ref "SJ1") (pin "1") (pinfunction "P$1_1") (pintype "passive"))
      (node (ref "SJ2") (pin "3") (pinfunction "3_3") (pintype "passive"))
    )
    (net (code "44") (name "VX") (class "Default")
      (node (ref "C02O") (pin "1") (pinfunction "1_1") (pintype "passive"))
      (node (ref "R01C") (pin "2") (pinfunction "2_2") (pintype "passive"))
      (node (ref "R01L") (pin "2") (pinfunction "2_2") (pintype "passive"))
      (node (ref "R01V") (pin "1") (pinfunction "1_1") (pintype "passive"))
      (node (ref "R02F") (pin "1") (pinfunction "1_1") (pintype "passive"))
      (node (ref "R02L") (pin "1") (pinfunction "1_1") (pintype "passive"))
      (node (ref "SJ2") (pin "1") (pinfunction "1_1") (pintype "passive"))
      (node (ref "SJ4") (pin "3") (pinfunction "3_3") (pintype "passive"))
    )
    (net (code "45") (name "unconnected-(J01U-4.ID-Pad4)") (class "Default")
      (node (ref "J01U") (pin "4") (pinfunction "4.ID_4") (pintype "passive"))
    )
    (net (code "46") (name "unconnected-(U10-1.VDD-Pad1)") (class "Default")
      (node (ref "U10") (pin "1") (pinfunction "1.VDD_1") (pintype "passive"))
    )
    (net (code "47") (name "unconnected-(U10-3.PC14-Pad3)") (class "Default")
      (node (ref "U10") (pin "3") (pinfunction "3.PC14_3") (pintype "passive"))
    )
    (net (code "48") (name "unconnected-(U10-4.PC15-Pad4)") (class "Default")
      (node (ref "U10") (pin "4") (pinfunction "4.PC15_4") (pintype "passive"))
    )
    (net (code "49") (name "unconnected-(U10-5.OSC_IN-Pad5)") (class "Default")
      (node (ref "U10") (pin "5") (pinfunction "5.OSC_IN_5") (pintype "passive"))
    )
    (net (code "50") (name "unconnected-(U10-6.OSC_OUT-Pad6)") (class "Default")
      (node (ref "U10") (pin "6") (pinfunction "6.OSC_OUT_6") (pintype "passive"))
    )
    (net (code "51") (name "unconnected-(U10-14.PA4-Pad14)") (class "Default")
      (node (ref "U10") (pin "14") (pinfunction "14.PA4_14") (pintype "passive"))
    )
    (net (code "52") (name "unconnected-(U10-15.PA5-Pad15)") (class "Default")
      (node (ref "U10") (pin "15") (pinfunction "15.PA5_15") (pintype "passive"))
    )
    (net (code "53") (name "unconnected-(U10-16.PA6-Pad16)") (class "Default")
      (node (ref "U10") (pin "16") (pinfunction "16.PA6_16") (pintype "passive"))
    )
    (net (code "54") (name "unconnected-(U10-17.PA7-Pad17)") (class "Default")
      (node (ref "U10") (pin "17") (pinfunction "17.PA7_17") (pintype "passive"))
    )
    (net (code "55") (name "unconnected-(U10-18.PB0-Pad18)") (class "Default")
      (node (ref "U10") (pin "18") (pinfunction "18.PB0_18") (pintype "passive"))
    )
    (net (code "56") (name "unconnected-(U10-19.PB1-Pad19)") (class "Default")
      (node (ref "U10") (pin "19") (pinfunction "19.PB1_19") (pintype "passive"))
    )
    (net (code "57") (name "unconnected-(U10-20.PB2-Pad20)") (class "Default")
      (node (ref "U10") (pin "20") (pinfunction "20.PB2_20") (pintype "passive"))
    )
    (net (code "58") (name "unconnected-(U10-21.PB10-Pad21)") (class "Default")
      (node (ref "U10") (pin "21") (pinfunction "21.PB10_21") (pintype "passive"))
    )
    (net (code "59") (name "unconnected-(U10-22.PB11-Pad22)") (class "Default")
      (node (ref "U10") (pin "22") (pinfunction "22.PB11_22") (pintype "passive"))
    )
    (net (code "60") (name "unconnected-(U10-25.PB12-Pad25)") (class "Default")
      (node (ref "U10") (pin "25") (pinfunction "25.PB12_25") (pintype "passive"))
    )
    (net (code "61") (name "unconnected-(U10-27.PB14-Pad27)") (class "Default")
      (node (ref "U10") (pin "27") (pinfunction "27.PB14_27") (pintype "passive"))
    )
    (net (code "62") (name "unconnected-(U10-28.PB15-Pad28)") (class "Default")
      (node (ref "U10") (pin "28") (pinfunction "28.PB15_28") (pintype "passive"))
    )
    (net (code "63") (name "unconnected-(U10-29.PA8-Pad29)") (class "Default")
      (node (ref "U10") (pin "29") (pinfunction "29.PA8_29") (pintype "passive"))
    )
    (net (code "64") (name "~{CLR}") (class "Default")
      (node (ref "SJ3") (pin "2") (pinfunction "P$2_2") (pintype "passive"))
      (node (ref "U03") (pin "9") (pinfunction "9.~{CLR}_9") (pintype "passive"))
      (node (ref "U10") (pin "45") (pinfunction "45.PB8_45") (pintype "passive"))
    )
    (net (code "65") (name "~{INT}") (class "Default")
      (node (ref "R11C") (pin "1") (pinfunction "1_1") (pintype "passive"))
      (node (ref "SJ3") (pin "1") (pinfunction "P$1_1") (pintype "passive"))
      (node (ref "U03") (pin "10") (pinfunction "10.~{INT}_10") (pintype "passive"))
      (node (ref "U10") (pin "10") (pinfunction "10.PA0_10") (pintype "passive"))
    )
    (net (code "66") (name "~{RST}") (class "Default")
      (node (ref "C10R") (pin "1") (pinfunction "1_1") (pintype "passive"))
      (node (ref "SW10R") (pin "1") (pinfunction "1-2_1") (pintype "passive"))
      (node (ref "U10") (pin "7") (pinfunction "7.~{RST}_7") (pintype "passive"))
    )
    (net (code "67") (name "~{SHDN}") (class "Default")
      (node (ref "U03") (pin "5") (pinfunction "5.~{SHDN}_5") (pintype "passive"))
      (node (ref "U10") (pin "40") (pinfunction "40.PB4_40") (pintype "passive"))
    )
  )
)
